# ESC-simple.net
KiCad netlist of a schematic drawn in EAGLE
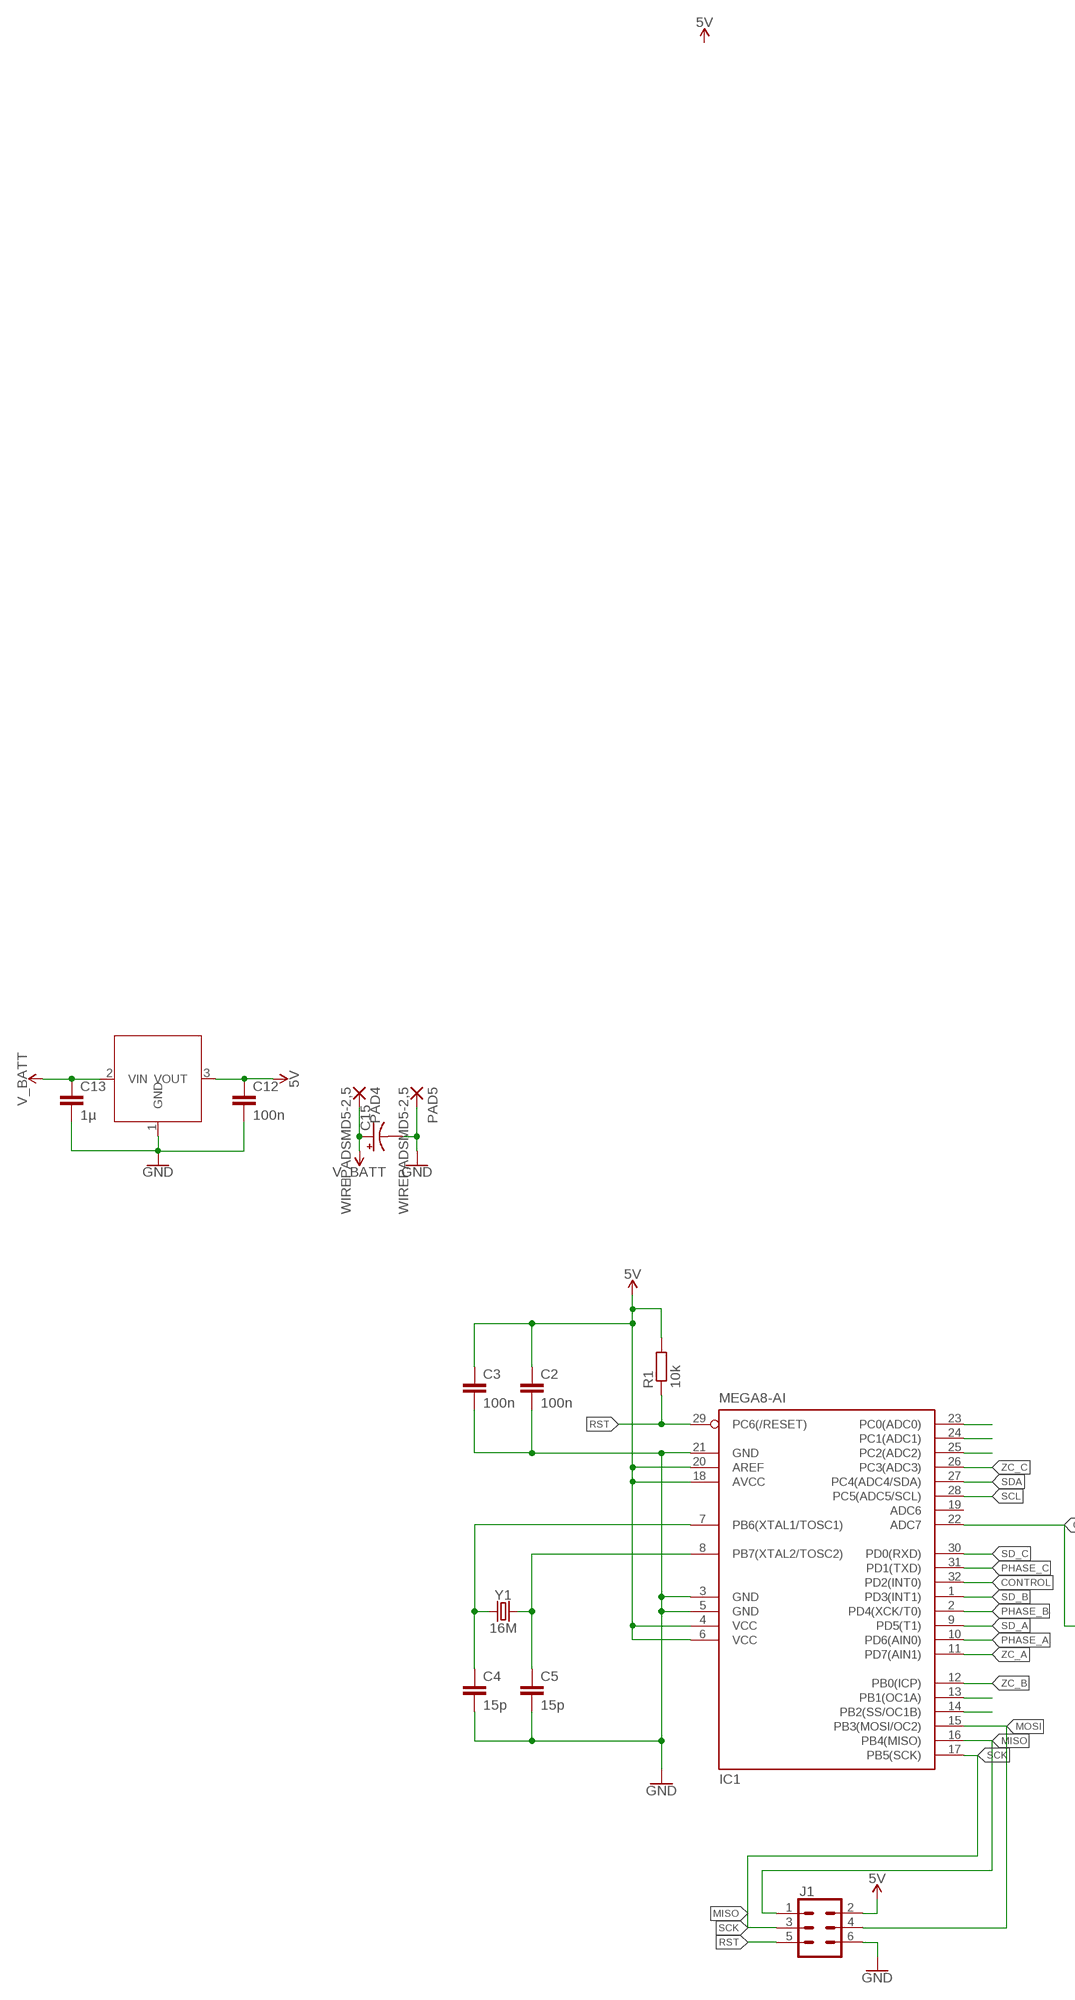
[diagram p0: schematic, sheet 1, part 1 of 2]
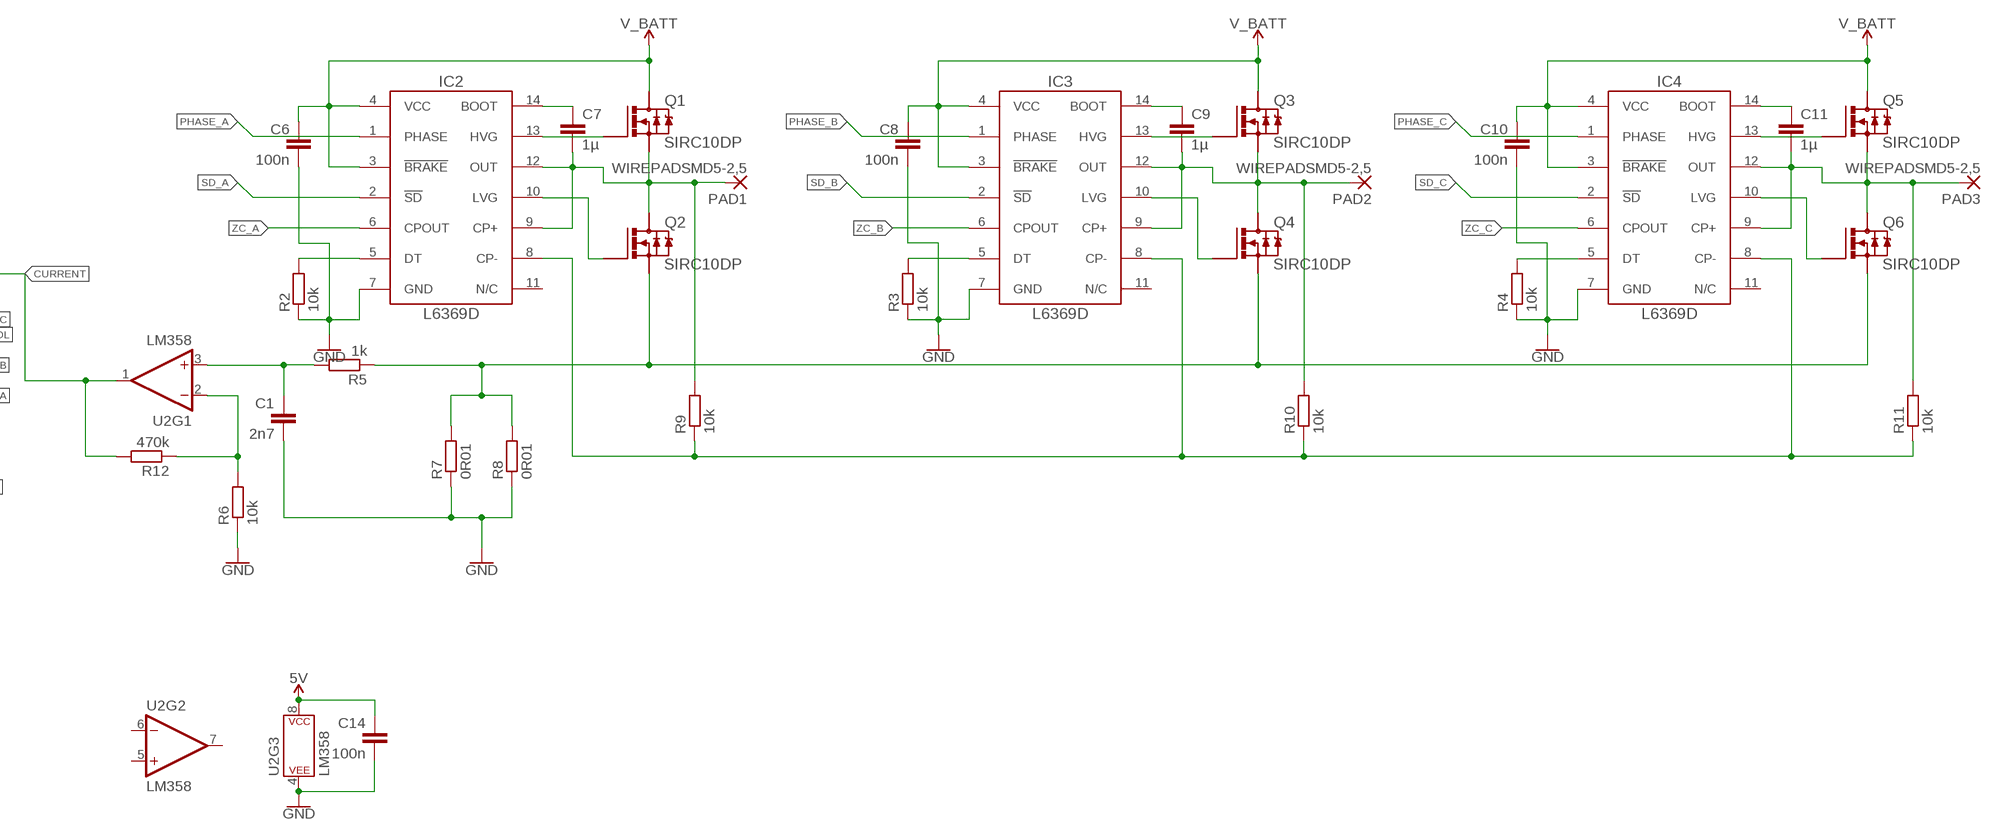
[diagram p1: schematic, sheet 1, part 2 of 2]

(export (version "E")
  (design (tool "Eeschema 10.0.6"))
  (components
    (comp (ref "C1")
      (value "2n7")
      (footprint "eagle-import:C1206K")
      (libsource (lib "eagle-import") (part "C-EUC1206K"))
    )
    (comp (ref "C2")
      (value "100n")
      (footprint "eagle-import:C1206K")
      (libsource (lib "eagle-import") (part "C-EUC1206K"))
    )
    (comp (ref "C3")
      (value "100n")
      (footprint "eagle-import:C1206K")
      (libsource (lib "eagle-import") (part "C-EUC1206K"))
    )
    (comp (ref "C4")
      (value "15p")
      (footprint "eagle-import:C1206K")
      (libsource (lib "eagle-import") (part "C-EUC1206K"))
    )
    (comp (ref "C5")
      (value "15p")
      (footprint "eagle-import:C1206K")
      (libsource (lib "eagle-import") (part "C-EUC1206K"))
    )
    (comp (ref "C6")
      (value "100n")
      (footprint "eagle-import:C1206K")
      (libsource (lib "eagle-import") (part "C-EUC1206K"))
    )
    (comp (ref "C7")
      (value "1µ")
      (footprint "eagle-import:C1206K")
      (libsource (lib "eagle-import") (part "C-EUC1206K"))
    )
    (comp (ref "C8")
      (value "100n")
      (footprint "eagle-import:C1206K")
      (libsource (lib "eagle-import") (part "C-EUC1206K"))
    )
    (comp (ref "C9")
      (value "1µ")
      (footprint "eagle-import:C1206K")
      (libsource (lib "eagle-import") (part "C-EUC1206K"))
    )
    (comp (ref "C10")
      (value "100n")
      (footprint "eagle-import:C1206K")
      (libsource (lib "eagle-import") (part "C-EUC1206K"))
    )
    (comp (ref "C11")
      (value "1µ")
      (footprint "eagle-import:C1206K")
      (libsource (lib "eagle-import") (part "C-EUC1206K"))
    )
    (comp (ref "C12")
      (value "100n")
      (footprint "eagle-import:C1206K")
      (libsource (lib "eagle-import") (part "C-EUC1206K"))
    )
    (comp (ref "C13")
      (value "1µ")
      (footprint "eagle-import:C1206K")
      (libsource (lib "eagle-import") (part "C-EUC1206K"))
    )
    (comp (ref "C14")
      (value "100n")
      (footprint "eagle-import:C1206K")
      (libsource (lib "eagle-import") (part "C-EUC1206K"))
    )
    (comp (ref "C15")
      (value "CPOL-USE5-13")
      (footprint "eagle-import:E5-13")
      (libsource (lib "eagle-import") (part "CPOL-USE5-13"))
    )
    (comp (ref "IC1")
      (value "MEGA8-AI")
      (footprint "eagle-import:TQFP32-08")
      (fields (field (name "MPN") "ATMEGA8-16AU"))
      (libsource (lib "eagle-import") (part "MEGA8-AI"))
    )
    (comp (ref "IC2")
      (value "L6369D")
      (footprint "eagle-import:SO-14")
      (libsource (lib "eagle-import") (part "L6369D"))
    )
    (comp (ref "IC3")
      (value "L6369D")
      (footprint "eagle-import:SO-14")
      (libsource (lib "eagle-import") (part "L6369D"))
    )
    (comp (ref "IC4")
      (value "L6369D")
      (footprint "eagle-import:SO-14")
      (libsource (lib "eagle-import") (part "L6369D"))
    )
    (comp (ref "J1")
      (value "CONN_03X22X3_SILK_MALE_PTH")
      (footprint "eagle-import:2X3")
      (libsource (lib "eagle-import") (part "CONN_03X22X3_SILK_MALE_PTH"))
    )
    (comp (ref "PAD1")
      (value "WIREPADSMD5-2,5")
      (footprint "eagle-import:5-2,5")
      (libsource (lib "eagle-import") (part "WIREPADSMD5-2,5"))
    )
    (comp (ref "PAD2")
      (value "WIREPADSMD5-2,5")
      (footprint "eagle-import:5-2,5")
      (libsource (lib "eagle-import") (part "WIREPADSMD5-2,5"))
    )
    (comp (ref "PAD3")
      (value "WIREPADSMD5-2,5")
      (footprint "eagle-import:5-2,5")
      (libsource (lib "eagle-import") (part "WIREPADSMD5-2,5"))
    )
    (comp (ref "PAD4")
      (value "WIREPADSMD5-2,5")
      (footprint "eagle-import:5-2,5")
      (libsource (lib "eagle-import") (part "WIREPADSMD5-2,5"))
    )
    (comp (ref "PAD5")
      (value "WIREPADSMD5-2,5")
      (footprint "eagle-import:5-2,5")
      (libsource (lib "eagle-import") (part "WIREPADSMD5-2,5"))
    )
    (comp (ref "Q1")
      (value "SIRC10DP")
      (footprint "eagle-import:POWERPAK_SO-8_SINGLE")
      (libsource (lib "eagle-import") (part "SIRC10DP"))
    )
    (comp (ref "Q2")
      (value "SIRC10DP")
      (footprint "eagle-import:POWERPAK_SO-8_SINGLE")
      (libsource (lib "eagle-import") (part "SIRC10DP"))
    )
    (comp (ref "Q3")
      (value "SIRC10DP")
      (footprint "eagle-import:POWERPAK_SO-8_SINGLE")
      (libsource (lib "eagle-import") (part "SIRC10DP"))
    )
    (comp (ref "Q4")
      (value "SIRC10DP")
      (footprint "eagle-import:POWERPAK_SO-8_SINGLE")
      (libsource (lib "eagle-import") (part "SIRC10DP"))
    )
    (comp (ref "Q5")
      (value "SIRC10DP")
      (footprint "eagle-import:POWERPAK_SO-8_SINGLE")
      (libsource (lib "eagle-import") (part "SIRC10DP"))
    )
    (comp (ref "Q6")
      (value "SIRC10DP")
      (footprint "eagle-import:POWERPAK_SO-8_SINGLE")
      (libsource (lib "eagle-import") (part "SIRC10DP"))
    )
    (comp (ref "R1")
      (value "10k")
      (footprint "eagle-import:R1206")
      (libsource (lib "eagle-import") (part "R-EU_R1206"))
    )
    (comp (ref "R2")
      (value "10k")
      (footprint "eagle-import:R1206")
      (libsource (lib "eagle-import") (part "R-EU_R1206"))
    )
    (comp (ref "R3")
      (value "10k")
      (footprint "eagle-import:R1206")
      (libsource (lib "eagle-import") (part "R-EU_R1206"))
    )
    (comp (ref "R4")
      (value "10k")
      (footprint "eagle-import:R1206")
      (libsource (lib "eagle-import") (part "R-EU_R1206"))
    )
    (comp (ref "R5")
      (value "1k")
      (footprint "eagle-import:R1206")
      (libsource (lib "eagle-import") (part "R-EU_R1206"))
    )
    (comp (ref "R6")
      (value "10k")
      (footprint "eagle-import:R1206")
      (libsource (lib "eagle-import") (part "R-EU_R1206"))
    )
    (comp (ref "R7")
      (value "0R01")
      (footprint "eagle-import:R1206")
      (libsource (lib "eagle-import") (part "R-EU_R1206"))
    )
    (comp (ref "R8")
      (value "0R01")
      (footprint "eagle-import:R1206")
      (libsource (lib "eagle-import") (part "R-EU_R1206"))
    )
    (comp (ref "R9")
      (value "10k")
      (footprint "eagle-import:R1206")
      (libsource (lib "eagle-import") (part "R-EU_R1206"))
    )
    (comp (ref "R10")
      (value "10k")
      (footprint "eagle-import:R1206")
      (libsource (lib "eagle-import") (part "R-EU_R1206"))
    )
    (comp (ref "R11")
      (value "10k")
      (footprint "eagle-import:R1206")
      (libsource (lib "eagle-import") (part "R-EU_R1206"))
    )
    (comp (ref "R12")
      (value "470k")
      (footprint "eagle-import:R1206")
      (libsource (lib "eagle-import") (part "R-EU_R1206"))
    )
    (comp (ref "U$1")
      (value "S812")
      (footprint "eagle-import:TO92L")
      (libsource (lib "eagle-import") (part "S812"))
    )
    (comp (ref "U2")
      (value "LM358")
      (footprint "eagle-import:DIP08")
      (libsource (lib "eagle-import") (part "LM358"))
    )
    (comp (ref "Y1")
      (value "16M")
      (footprint "eagle-import:HC49UP")
      (libsource (lib "eagle-import") (part "CRYSTALSMD-HC49UP"))
    )
  )
  (nets
    (net (code "1") (name "5V") (class "Default")
      (node (ref "C12") (pin "1") (pinfunction "1_1") (pintype "passive"))
      (node (ref "C14") (pin "1") (pinfunction "1_1") (pintype "passive"))
      (node (ref "C2") (pin "1") (pinfunction "1_1") (pintype "passive"))
      (node (ref "C3") (pin "1") (pinfunction "1_1") (pintype "passive"))
      (node (ref "IC1") (pin "18") (pinfunction "AVCC_18") (pintype "power_in"))
      (node (ref "IC1") (pin "20") (pinfunction "AREF_20") (pintype "passive"))
      (node (ref "IC1") (pin "4") (pinfunction "VCC_4") (pintype "power_in"))
      (node (ref "IC1") (pin "6") (pinfunction "VCC_6") (pintype "power_in"))
      (node (ref "J1") (pin "2") (pinfunction "2_2") (pintype "bidirectional"))
      (node (ref "R1") (pin "2") (pinfunction "2_2") (pintype "passive"))
      (node (ref "U$1") (pin "3") (pinfunction "VOUT_3") (pintype "power_in"))
      (node (ref "U2") (pin "8") (pinfunction "P$V+_8") (pintype "bidirectional"))
    )
    (net (code "2") (name "CONTROL") (class "Default")
      (node (ref "IC1") (pin "32") (pinfunction "PD2(INT0)_32") (pintype "bidirectional"))
    )
    (net (code "3") (name "CURRENT") (class "Default")
      (node (ref "IC1") (pin "22") (pinfunction "ADC7_22") (pintype "bidirectional"))
      (node (ref "R12") (pin "2") (pinfunction "2_2") (pintype "passive"))
      (node (ref "U2") (pin "1") (pinfunction "OUT_1") (pintype "output"))
    )
    (net (code "4") (name "GND") (class "Default")
      (node (ref "C1") (pin "2") (pinfunction "2_2") (pintype "passive"))
      (node (ref "C10") (pin "2") (pinfunction "2_2") (pintype "passive"))
      (node (ref "C12") (pin "2") (pinfunction "2_2") (pintype "passive"))
      (node (ref "C13") (pin "2") (pinfunction "2_2") (pintype "passive"))
      (node (ref "C14") (pin "2") (pinfunction "2_2") (pintype "passive"))
      (node (ref "C15") (pin "-") (pinfunction "-_-") (pintype "passive"))
      (node (ref "C2") (pin "2") (pinfunction "2_2") (pintype "passive"))
      (node (ref "C3") (pin "2") (pinfunction "2_2") (pintype "passive"))
      (node (ref "C4") (pin "2") (pinfunction "2_2") (pintype "passive"))
      (node (ref "C5") (pin "2") (pinfunction "2_2") (pintype "passive"))
      (node (ref "C6") (pin "2") (pinfunction "2_2") (pintype "passive"))
      (node (ref "C8") (pin "2") (pinfunction "2_2") (pintype "passive"))
      (node (ref "IC1") (pin "21") (pinfunction "GND_21") (pintype "power_in"))
      (node (ref "IC1") (pin "3") (pinfunction "GND_3") (pintype "power_in"))
      (node (ref "IC1") (pin "5") (pinfunction "GND_5") (pintype "power_in"))
      (node (ref "IC2") (pin "7") (pinfunction "GND_7") (pintype "power_in"))
      (node (ref "IC3") (pin "7") (pinfunction "GND_7") (pintype "power_in"))
      (node (ref "IC4") (pin "7") (pinfunction "GND_7") (pintype "power_in"))
      (node (ref "J1") (pin "6") (pinfunction "6_6") (pintype "bidirectional"))
      (node (ref "PAD5") (pin "1") (pinfunction "P_1") (pintype "passive"))
      (node (ref "R2") (pin "1") (pinfunction "1_1") (pintype "passive"))
      (node (ref "R3") (pin "1") (pinfunction "1_1") (pintype "passive"))
      (node (ref "R4") (pin "1") (pinfunction "1_1") (pintype "passive"))
      (node (ref "R6") (pin "1") (pinfunction "1_1") (pintype "passive"))
      (node (ref "R7") (pin "1") (pinfunction "1_1") (pintype "passive"))
      (node (ref "R8") (pin "1") (pinfunction "1_1") (pintype "passive"))
      (node (ref "U$1") (pin "1") (pinfunction "GND_1") (pintype "power_in"))
      (node (ref "U2") (pin "4") (pinfunction "P$V-_4") (pintype "bidirectional"))
    )
    (net (code "5") (name "MISO") (class "Default")
      (node (ref "IC1") (pin "16") (pinfunction "PB4(MISO)_16") (pintype "bidirectional"))
      (node (ref "J1") (pin "1") (pinfunction "1_1") (pintype "bidirectional"))
    )
    (net (code "6") (name "MOSI") (class "Default")
      (node (ref "IC1") (pin "15") (pinfunction "PB3(MOSI/OC2)_15") (pintype "bidirectional"))
      (node (ref "J1") (pin "4") (pinfunction "4_4") (pintype "bidirectional"))
    )
    (net (code "7") (name "Net-(IC1-PB6(XTAL1{slash}TOSC1))") (class "Default")
      (node (ref "C4") (pin "1") (pinfunction "1_1") (pintype "passive"))
      (node (ref "IC1") (pin "7") (pinfunction "PB6(XTAL1/TOSC1)_7") (pintype "bidirectional"))
      (node (ref "Y1") (pin "1") (pinfunction "1_1") (pintype "passive"))
    )
    (net (code "8") (name "Net-(IC1-PB7(XTAL2{slash}TOSC2))") (class "Default")
      (node (ref "C5") (pin "1") (pinfunction "1_1") (pintype "passive"))
      (node (ref "IC1") (pin "8") (pinfunction "PB7(XTAL2/TOSC2)_8") (pintype "bidirectional"))
      (node (ref "Y1") (pin "2") (pinfunction "2_2") (pintype "passive"))
    )
    (net (code "9") (name "Net-(IC2-BOOT)") (class "Default")
      (node (ref "C7") (pin "1") (pinfunction "1_1") (pintype "passive"))
      (node (ref "IC2") (pin "14") (pinfunction "BOOT_14") (pintype "power_in"))
    )
    (net (code "10") (name "Net-(IC2-CP+)") (class "Default")
      (node (ref "C7") (pin "2") (pinfunction "2_2") (pintype "passive"))
      (node (ref "IC2") (pin "12") (pinfunction "OUT_12") (pintype "output"))
      (node (ref "IC2") (pin "9") (pinfunction "CP+_9") (pintype "input"))
      (node (ref "PAD1") (pin "1") (pinfunction "P_1") (pintype "passive"))
      (node (ref "Q1") (pin "1") (pinfunction "S_1") (pintype "bidirectional"))
      (node (ref "Q1") (pin "2") (pinfunction "S_2") (pintype "bidirectional"))
      (node (ref "Q1") (pin "3") (pinfunction "S_3") (pintype "bidirectional"))
      (node (ref "Q2") (pin "5") (pinfunction "D_5") (pintype "bidirectional"))
      (node (ref "Q2") (pin "6") (pinfunction "D_6") (pintype "bidirectional"))
      (node (ref "Q2") (pin "7") (pinfunction "D_7") (pintype "bidirectional"))
      (node (ref "Q2") (pin "8") (pinfunction "D_8") (pintype "bidirectional"))
      (node (ref "Q2") (pin "9") (pinfunction "D_9") (pintype "bidirectional"))
      (node (ref "R9") (pin "2") (pinfunction "2_2") (pintype "passive"))
    )
    (net (code "11") (name "Net-(IC2-CP-)") (class "Default")
      (node (ref "IC2") (pin "8") (pinfunction "CP-_8") (pintype "input"))
      (node (ref "IC3") (pin "8") (pinfunction "CP-_8") (pintype "input"))
      (node (ref "IC4") (pin "8") (pinfunction "CP-_8") (pintype "input"))
      (node (ref "R10") (pin "1") (pinfunction "1_1") (pintype "passive"))
      (node (ref "R11") (pin "1") (pinfunction "1_1") (pintype "passive"))
      (node (ref "R9") (pin "1") (pinfunction "1_1") (pintype "passive"))
    )
    (net (code "12") (name "Net-(IC2-DT)") (class "Default")
      (node (ref "IC2") (pin "5") (pinfunction "DT_5") (pintype "input"))
      (node (ref "R2") (pin "2") (pinfunction "2_2") (pintype "passive"))
    )
    (net (code "13") (name "Net-(IC2-HVG)") (class "Default")
      (node (ref "IC2") (pin "13") (pinfunction "HVG_13") (pintype "output"))
      (node (ref "Q1") (pin "4") (pinfunction "G_4") (pintype "bidirectional"))
    )
    (net (code "14") (name "Net-(IC2-LVG)") (class "Default")
      (node (ref "IC2") (pin "10") (pinfunction "LVG_10") (pintype "output"))
      (node (ref "Q2") (pin "4") (pinfunction "G_4") (pintype "bidirectional"))
    )
    (net (code "15") (name "Net-(IC3-BOOT)") (class "Default")
      (node (ref "C9") (pin "1") (pinfunction "1_1") (pintype "passive"))
      (node (ref "IC3") (pin "14") (pinfunction "BOOT_14") (pintype "power_in"))
    )
    (net (code "16") (name "Net-(IC3-CP+)") (class "Default")
      (node (ref "C9") (pin "2") (pinfunction "2_2") (pintype "passive"))
      (node (ref "IC3") (pin "12") (pinfunction "OUT_12") (pintype "output"))
      (node (ref "IC3") (pin "9") (pinfunction "CP+_9") (pintype "input"))
      (node (ref "PAD2") (pin "1") (pinfunction "P_1") (pintype "passive"))
      (node (ref "Q3") (pin "1") (pinfunction "S_1") (pintype "bidirectional"))
      (node (ref "Q3") (pin "2") (pinfunction "S_2") (pintype "bidirectional"))
      (node (ref "Q3") (pin "3") (pinfunction "S_3") (pintype "bidirectional"))
      (node (ref "Q4") (pin "5") (pinfunction "D_5") (pintype "bidirectional"))
      (node (ref "Q4") (pin "6") (pinfunction "D_6") (pintype "bidirectional"))
      (node (ref "Q4") (pin "7") (pinfunction "D_7") (pintype "bidirectional"))
      (node (ref "Q4") (pin "8") (pinfunction "D_8") (pintype "bidirectional"))
      (node (ref "Q4") (pin "9") (pinfunction "D_9") (pintype "bidirectional"))
      (node (ref "R10") (pin "2") (pinfunction "2_2") (pintype "passive"))
    )
    (net (code "17") (name "Net-(IC3-DT)") (class "Default")
      (node (ref "IC3") (pin "5") (pinfunction "DT_5") (pintype "input"))
      (node (ref "R3") (pin "2") (pinfunction "2_2") (pintype "passive"))
    )
    (net (code "18") (name "Net-(IC3-HVG)") (class "Default")
      (node (ref "IC3") (pin "13") (pinfunction "HVG_13") (pintype "output"))
      (node (ref "Q3") (pin "4") (pinfunction "G_4") (pintype "bidirectional"))
    )
    (net (code "19") (name "Net-(IC3-LVG)") (class "Default")
      (node (ref "IC3") (pin "10") (pinfunction "LVG_10") (pintype "output"))
      (node (ref "Q4") (pin "4") (pinfunction "G_4") (pintype "bidirectional"))
    )
    (net (code "20") (name "Net-(IC4-BOOT)") (class "Default")
      (node (ref "C11") (pin "1") (pinfunction "1_1") (pintype "passive"))
      (node (ref "IC4") (pin "14") (pinfunction "BOOT_14") (pintype "power_in"))
    )
    (net (code "21") (name "Net-(IC4-CP+)") (class "Default")
      (node (ref "C11") (pin "2") (pinfunction "2_2") (pintype "passive"))
      (node (ref "IC4") (pin "12") (pinfunction "OUT_12") (pintype "output"))
      (node (ref "IC4") (pin "9") (pinfunction "CP+_9") (pintype "input"))
      (node (ref "PAD3") (pin "1") (pinfunction "P_1") (pintype "passive"))
      (node (ref "Q5") (pin "1") (pinfunction "S_1") (pintype "bidirectional"))
      (node (ref "Q5") (pin "2") (pinfunction "S_2") (pintype "bidirectional"))
      (node (ref "Q5") (pin "3") (pinfunction "S_3") (pintype "bidirectional"))
      (node (ref "Q6") (pin "5") (pinfunction "D_5") (pintype "bidirectional"))
      (node (ref "Q6") (pin "6") (pinfunction "D_6") (pintype "bidirectional"))
      (node (ref "Q6") (pin "7") (pinfunction "D_7") (pintype "bidirectional"))
      (node (ref "Q6") (pin "8") (pinfunction "D_8") (pintype "bidirectional"))
      (node (ref "Q6") (pin "9") (pinfunction "D_9") (pintype "bidirectional"))
      (node (ref "R11") (pin "2") (pinfunction "2_2") (pintype "passive"))
    )
    (net (code "22") (name "Net-(IC4-DT)") (class "Default")
      (node (ref "IC4") (pin "5") (pinfunction "DT_5") (pintype "input"))
      (node (ref "R4") (pin "2") (pinfunction "2_2") (pintype "passive"))
    )
    (net (code "23") (name "Net-(IC4-HVG)") (class "Default")
      (node (ref "IC4") (pin "13") (pinfunction "HVG_13") (pintype "output"))
      (node (ref "Q5") (pin "4") (pinfunction "G_4") (pintype "bidirectional"))
    )
    (net (code "24") (name "Net-(IC4-LVG)") (class "Default")
      (node (ref "IC4") (pin "10") (pinfunction "LVG_10") (pintype "output"))
      (node (ref "Q6") (pin "4") (pinfunction "G_4") (pintype "bidirectional"))
    )
    (net (code "25") (name "Net-(Q2-S-Pad1)") (class "Default")
      (node (ref "Q2") (pin "1") (pinfunction "S_1") (pintype "bidirectional"))
      (node (ref "Q2") (pin "2") (pinfunction "S_2") (pintype "bidirectional"))
      (node (ref "Q2") (pin "3") (pinfunction "S_3") (pintype "bidirectional"))
      (node (ref "Q4") (pin "1") (pinfunction "S_1") (pintype "bidirectional"))
      (node (ref "Q4") (pin "2") (pinfunction "S_2") (pintype "bidirectional"))
      (node (ref "Q4") (pin "3") (pinfunction "S_3") (pintype "bidirectional"))
      (node (ref "Q6") (pin "1") (pinfunction "S_1") (pintype "bidirectional"))
      (node (ref "Q6") (pin "2") (pinfunction "S_2") (pintype "bidirectional"))
      (node (ref "Q6") (pin "3") (pinfunction "S_3") (pintype "bidirectional"))
      (node (ref "R5") (pin "1") (pinfunction "1_1") (pintype "passive"))
      (node (ref "R7") (pin "2") (pinfunction "2_2") (pintype "passive"))
      (node (ref "R8") (pin "2") (pinfunction "2_2") (pintype "passive"))
    )
    (net (code "26") (name "Net-(U2A-+IN)") (class "Default")
      (node (ref "C1") (pin "1") (pinfunction "1_1") (pintype "passive"))
      (node (ref "R5") (pin "2") (pinfunction "2_2") (pintype "passive"))
      (node (ref "U2") (pin "3") (pinfunction "+IN_3") (pintype "input"))
    )
    (net (code "27") (name "Net-(U2A--IN)") (class "Default")
      (node (ref "R12") (pin "1") (pinfunction "1_1") (pintype "passive"))
      (node (ref "R6") (pin "2") (pinfunction "2_2") (pintype "passive"))
      (node (ref "U2") (pin "2") (pinfunction "-IN_2") (pintype "input"))
    )
    (net (code "28") (name "PHASE_A") (class "Default")
      (node (ref "IC1") (pin "10") (pinfunction "PD6(AIN0)_10") (pintype "bidirectional"))
      (node (ref "IC2") (pin "1") (pinfunction "PHASE_1") (pintype "input"))
    )
    (net (code "29") (name "PHASE_B") (class "Default")
      (node (ref "IC1") (pin "2") (pinfunction "PD4(XCK/T0)_2") (pintype "bidirectional"))
      (node (ref "IC3") (pin "1") (pinfunction "PHASE_1") (pintype "input"))
    )
    (net (code "30") (name "PHASE_C") (class "Default")
      (node (ref "IC1") (pin "31") (pinfunction "PD1(TXD)_31") (pintype "bidirectional"))
      (node (ref "IC4") (pin "1") (pinfunction "PHASE_1") (pintype "input"))
    )
    (net (code "31") (name "RST") (class "Default")
      (node (ref "IC1") (pin "29") (pinfunction "PC6(/RESET)_29") (pintype "bidirectional"))
      (node (ref "J1") (pin "5") (pinfunction "5_5") (pintype "bidirectional"))
      (node (ref "R1") (pin "1") (pinfunction "1_1") (pintype "passive"))
    )
    (net (code "32") (name "SCK") (class "Default")
      (node (ref "IC1") (pin "17") (pinfunction "PB5(SCK)_17") (pintype "bidirectional"))
      (node (ref "J1") (pin "3") (pinfunction "3_3") (pintype "bidirectional"))
    )
    (net (code "33") (name "SCL") (class "Default")
      (node (ref "IC1") (pin "28") (pinfunction "PC5(ADC5/SCL)_28") (pintype "bidirectional"))
    )
    (net (code "34") (name "SDA") (class "Default")
      (node (ref "IC1") (pin "27") (pinfunction "PC4(ADC4/SDA)_27") (pintype "bidirectional"))
    )
    (net (code "35") (name "SD_A") (class "Default")
      (node (ref "IC1") (pin "9") (pinfunction "PD5(T1)_9") (pintype "bidirectional"))
      (node (ref "IC2") (pin "2") (pinfunction "~{SD}_2") (pintype "input"))
    )
    (net (code "36") (name "SD_B") (class "Default")
      (node (ref "IC1") (pin "1") (pinfunction "PD3(INT1)_1") (pintype "bidirectional"))
      (node (ref "IC3") (pin "2") (pinfunction "~{SD}_2") (pintype "input"))
    )
    (net (code "37") (name "SD_C") (class "Default")
      (node (ref "IC1") (pin "30") (pinfunction "PD0(RXD)_30") (pintype "bidirectional"))
      (node (ref "IC4") (pin "2") (pinfunction "~{SD}_2") (pintype "input"))
    )
    (net (code "38") (name "V_BATT") (class "Default")
      (node (ref "C10") (pin "1") (pinfunction "1_1") (pintype "passive"))
      (node (ref "C13") (pin "1") (pinfunction "1_1") (pintype "passive"))
      (node (ref "C15") (pin "+") (pinfunction "+_+") (pintype "passive"))
      (node (ref "C6") (pin "1") (pinfunction "1_1") (pintype "passive"))
      (node (ref "C8") (pin "1") (pinfunction "1_1") (pintype "passive"))
      (node (ref "IC2") (pin "3") (pinfunction "~{BRAKE}_3") (pintype "input"))
      (node (ref "IC2") (pin "4") (pinfunction "VCC_4") (pintype "power_in"))
      (node (ref "IC3") (pin "3") (pinfunction "~{BRAKE}_3") (pintype "input"))
      (node (ref "IC3") (pin "4") (pinfunction "VCC_4") (pintype "power_in"))
      (node (ref "IC4") (pin "3") (pinfunction "~{BRAKE}_3") (pintype "input"))
      (node (ref "IC4") (pin "4") (pinfunction "VCC_4") (pintype "power_in"))
      (node (ref "PAD4") (pin "1") (pinfunction "P_1") (pintype "passive"))
      (node (ref "Q1") (pin "5") (pinfunction "D_5") (pintype "bidirectional"))
      (node (ref "Q1") (pin "6") (pinfunction "D_6") (pintype "bidirectional"))
      (node (ref "Q1") (pin "7") (pinfunction "D_7") (pintype "bidirectional"))
      (node (ref "Q1") (pin "8") (pinfunction "D_8") (pintype "bidirectional"))
      (node (ref "Q1") (pin "9") (pinfunction "D_9") (pintype "bidirectional"))
      (node (ref "Q3") (pin "5") (pinfunction "D_5") (pintype "bidirectional"))
      (node (ref "Q3") (pin "6") (pinfunction "D_6") (pintype "bidirectional"))
      (node (ref "Q3") (pin "7") (pinfunction "D_7") (pintype "bidirectional"))
      (node (ref "Q3") (pin "8") (pinfunction "D_8") (pintype "bidirectional"))
      (node (ref "Q3") (pin "9") (pinfunction "D_9") (pintype "bidirectional"))
      (node (ref "Q5") (pin "5") (pinfunction "D_5") (pintype "bidirectional"))
      (node (ref "Q5") (pin "6") (pinfunction "D_6") (pintype "bidirectional"))
      (node (ref "Q5") (pin "7") (pinfunction "D_7") (pintype "bidirectional"))
      (node (ref "Q5") (pin "8") (pinfunction "D_8") (pintype "bidirectional"))
      (node (ref "Q5") (pin "9") (pinfunction "D_9") (pintype "bidirectional"))
      (node (ref "U$1") (pin "2") (pinfunction "VIN_2") (pintype "power_in"))
    )
    (net (code "39") (name "ZC_A") (class "Default")
      (node (ref "IC1") (pin "11") (pinfunction "PD7(AIN1)_11") (pintype "bidirectional"))
      (node (ref "IC2") (pin "6") (pinfunction "CPOUT_6") (pintype "output"))
    )
    (net (code "40") (name "ZC_B") (class "Default")
      (node (ref "IC1") (pin "12") (pinfunction "PB0(ICP)_12") (pintype "bidirectional"))
      (node (ref "IC3") (pin "6") (pinfunction "CPOUT_6") (pintype "output"))
    )
    (net (code "41") (name "ZC_C") (class "Default")
      (node (ref "IC1") (pin "26") (pinfunction "PC3(ADC3)_26") (pintype "bidirectional"))
      (node (ref "IC4") (pin "6") (pinfunction "CPOUT_6") (pintype "output"))
    )
    (net (code "42") (name "unconnected-(IC1-ADC6-Pad19)") (class "Default")
      (node (ref "IC1") (pin "19") (pinfunction "ADC6_19") (pintype "bidirectional"))
    )
    (net (code "43") (name "unconnected-(IC1-PB1(OC1A)-Pad13)") (class "Default")
      (node (ref "IC1") (pin "13") (pinfunction "PB1(OC1A)_13") (pintype "bidirectional"))
    )
    (net (code "44") (name "unconnected-(IC1-PB2(SS{slash}OC1B)-Pad14)") (class "Default")
      (node (ref "IC1") (pin "14") (pinfunction "PB2(SS/OC1B)_14") (pintype "bidirectional"))
    )
    (net (code "45") (name "unconnected-(IC1-PC0(ADC0)-Pad23)") (class "Default")
      (node (ref "IC1") (pin "23") (pinfunction "PC0(ADC0)_23") (pintype "bidirectional"))
    )
    (net (code "46") (name "unconnected-(IC1-PC1(ADC1)-Pad24)") (class "Default")
      (node (ref "IC1") (pin "24") (pinfunction "PC1(ADC1)_24") (pintype "bidirectional"))
    )
    (net (code "47") (name "unconnected-(IC1-PC2(ADC2)-Pad25)") (class "Default")
      (node (ref "IC1") (pin "25") (pinfunction "PC2(ADC2)_25") (pintype "bidirectional"))
    )
    (net (code "48") (name "unconnected-(IC2-N{slash}C-Pad11)") (class "Default")
      (node (ref "IC2") (pin "11") (pinfunction "N/C_11") (pintype "no_connect"))
    )
    (net (code "49") (name "unconnected-(IC3-N{slash}C-Pad11)") (class "Default")
      (node (ref "IC3") (pin "11") (pinfunction "N/C_11") (pintype "no_connect"))
    )
    (net (code "50") (name "unconnected-(IC4-N{slash}C-Pad11)") (class "Default")
      (node (ref "IC4") (pin "11") (pinfunction "N/C_11") (pintype "no_connect"))
    )
    (net (code "51") (name "unconnected-(U2B-+IN-Pad5)") (class "Default")
      (node (ref "U2") (pin "5") (pinfunction "+IN_5") (pintype "input"))
    )
    (net (code "52") (name "unconnected-(U2B--IN-Pad6)") (class "Default")
      (node (ref "U2") (pin "6") (pinfunction "-IN_6") (pintype "input"))
    )
    (net (code "53") (name "unconnected-(U2B-OUT-Pad7)") (class "Default")
      (node (ref "U2") (pin "7") (pinfunction "OUT_7") (pintype "output"))
    )
  )
)
